# chariot_comms_a2.net
KiCad netlist of a schematic drawn in EAGLE
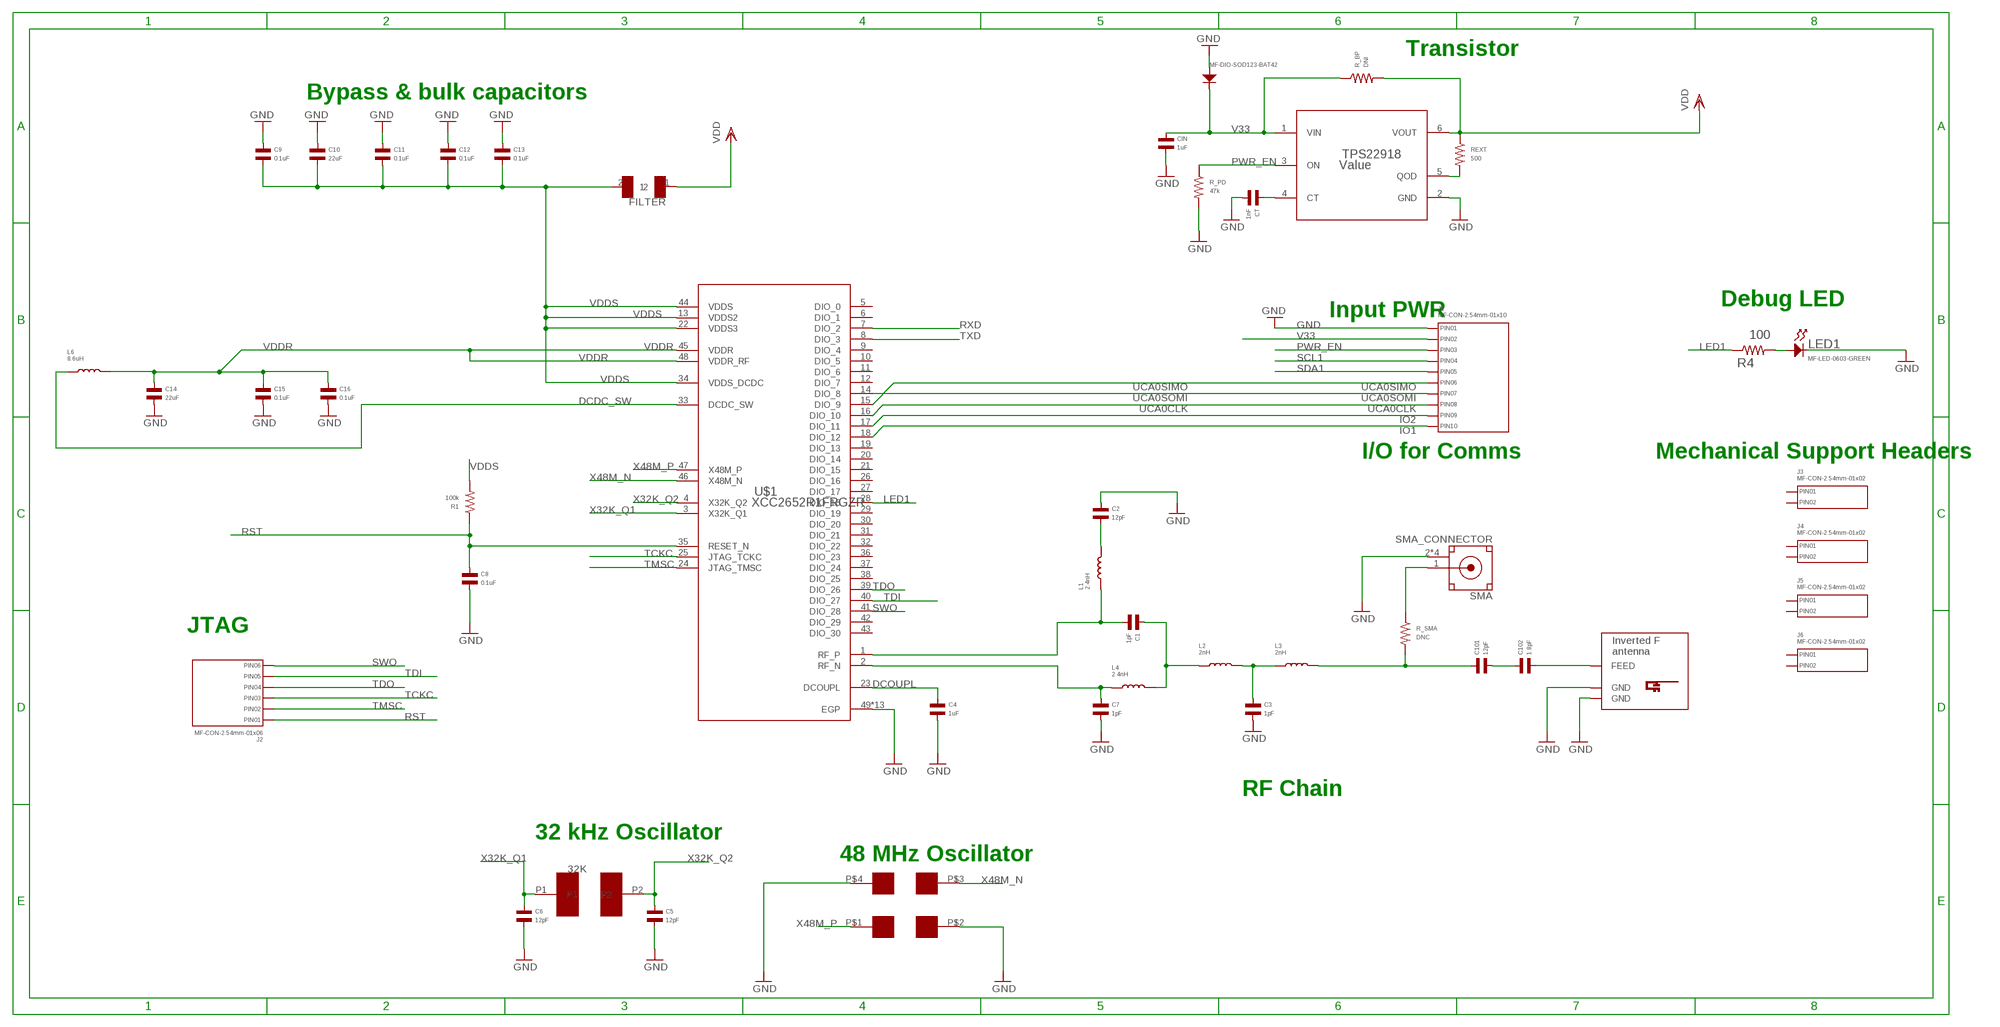
[diagram p0: schematic, sheet 1]

(export (version "E")
  (design (tool "Eeschema 10.0.6"))
  (components
    (comp (ref "32K")
      (value "FC-135")
      (footprint "eagle-import:FC-135")
      (libsource (lib "eagle-import") (part "FC-135"))
    )
    (comp (ref "48M")
      (value "NX2016SA-48M-EXS00A-CS05517")
      (footprint "eagle-import:NX2016SA-48M-EXS00A-CS05517")
      (libsource (lib "eagle-import") (part "NX2016SA-48M-EXS00A-CS05517"))
    )
    (comp (ref "C1")
      (value "1pF")
      (footprint "eagle-import:C0603")
      (libsource (lib "eagle-import") (part "CAPACITOR_NP_0603"))
    )
    (comp (ref "C2")
      (value "12pF")
      (footprint "eagle-import:C0603")
      (libsource (lib "eagle-import") (part "CAPACITOR_NP_0603"))
    )
    (comp (ref "C3")
      (value "1pF")
      (footprint "eagle-import:C0603")
      (libsource (lib "eagle-import") (part "CAPACITOR_NP_0603"))
    )
    (comp (ref "C4")
      (value "1uF")
      (footprint "eagle-import:C0603")
      (libsource (lib "eagle-import") (part "CAPACITOR_NP_0603"))
    )
    (comp (ref "C5")
      (value "12pF")
      (footprint "eagle-import:C0603")
      (libsource (lib "eagle-import") (part "CAPACITOR_NP_0603"))
    )
    (comp (ref "C6")
      (value "12pF")
      (footprint "eagle-import:C0603")
      (libsource (lib "eagle-import") (part "CAPACITOR_NP_0603"))
    )
    (comp (ref "C7")
      (value "1pF")
      (footprint "eagle-import:C0603")
      (libsource (lib "eagle-import") (part "CAPACITOR_NP_0603"))
    )
    (comp (ref "C8")
      (value "0.1uF")
      (footprint "eagle-import:C0603")
      (libsource (lib "eagle-import") (part "CAPACITOR_NP_0603"))
    )
    (comp (ref "C9")
      (value "0.1uF")
      (footprint "eagle-import:C0603")
      (libsource (lib "eagle-import") (part "CAPACITOR_NP_0603"))
    )
    (comp (ref "C10")
      (value "22uF")
      (footprint "eagle-import:C0603")
      (libsource (lib "eagle-import") (part "CAPACITOR_NP_0603"))
    )
    (comp (ref "C11")
      (value "0.1uF")
      (footprint "eagle-import:C0603")
      (libsource (lib "eagle-import") (part "CAPACITOR_NP_0603"))
    )
    (comp (ref "C12")
      (value "0.1uF")
      (footprint "eagle-import:C0603")
      (libsource (lib "eagle-import") (part "CAPACITOR_NP_0603"))
    )
    (comp (ref "C13")
      (value "0.1uF")
      (footprint "eagle-import:C0603")
      (libsource (lib "eagle-import") (part "CAPACITOR_NP_0603"))
    )
    (comp (ref "C14")
      (value "22uF")
      (footprint "eagle-import:C0603")
      (libsource (lib "eagle-import") (part "CAPACITOR_NP_0603"))
    )
    (comp (ref "C15")
      (value "0.1uF")
      (footprint "eagle-import:C0603")
      (libsource (lib "eagle-import") (part "CAPACITOR_NP_0603"))
    )
    (comp (ref "C16")
      (value "0.1uF")
      (footprint "eagle-import:C0603")
      (libsource (lib "eagle-import") (part "CAPACITOR_NP_0603"))
    )
    (comp (ref "C101")
      (value "12pF")
      (footprint "eagle-import:C0603")
      (libsource (lib "eagle-import") (part "CAPACITOR_NP_0603"))
    )
    (comp (ref "C102")
      (value "1.8pF")
      (footprint "eagle-import:C0603")
      (libsource (lib "eagle-import") (part "CAPACITOR_NP_0603"))
    )
    (comp (ref "CIN")
      (value "1uF")
      (footprint "eagle-import:C0603")
      (libsource (lib "eagle-import") (part "CAPACITOR_NP_0603"))
    )
    (comp (ref "CT")
      (value "1nF")
      (footprint "eagle-import:C0603")
      (libsource (lib "eagle-import") (part "CAPACITOR_NP_0603"))
    )
    (comp (ref "D1")
      (value "MF-DIO-SOD123-BAT42")
      (footprint "eagle-import:SOD-123")
      (fields (field (name "HOUSEPART") "YES"))
      (libsource (lib "eagle-import") (part "DIODES_SOD-123_BAT42"))
    )
    (comp (ref "FILTER")
      (value "BLM18")
      (footprint "eagle-import:BLM18")
      (libsource (lib "eagle-import") (part "BLM18"))
    )
    (comp (ref "J1")
      (value "MF-CON-2.54mm-01x10")
      (footprint "eagle-import:PTH_2.54MM_01X10")
      (fields (field (name "HOUSEPART") "YES"))
      (libsource (lib "eagle-import") (part "CON_01X10_PTH_2.54MM"))
    )
    (comp (ref "J2")
      (value "MF-CON-2.54mm-01x06")
      (footprint "eagle-import:PTH_2.54MM_01X06")
      (fields (field (name "HOUSEPART") "YES"))
      (libsource (lib "eagle-import") (part "CON_01X06_PTH_2.54MM"))
    )
    (comp (ref "J3")
      (value "MF-CON-2.54mm-01x02")
      (footprint "eagle-import:PTH_2.54MM_01X02")
      (fields (field (name "HOUSEPART") "YES"))
      (libsource (lib "eagle-import") (part "CON_01X02_PTH_2.54MM"))
    )
    (comp (ref "J4")
      (value "MF-CON-2.54mm-01x02")
      (footprint "eagle-import:PTH_2.54MM_01X02")
      (fields (field (name "HOUSEPART") "YES"))
      (libsource (lib "eagle-import") (part "CON_01X02_PTH_2.54MM"))
    )
    (comp (ref "J5")
      (value "MF-CON-2.54mm-01x02")
      (footprint "eagle-import:PTH_2.54MM_01X02")
      (fields (field (name "HOUSEPART") "YES"))
      (libsource (lib "eagle-import") (part "CON_01X02_PTH_2.54MM"))
    )
    (comp (ref "J6")
      (value "MF-CON-2.54mm-01x02")
      (footprint "eagle-import:PTH_2.54MM_01X02")
      (fields (field (name "HOUSEPART") "YES"))
      (libsource (lib "eagle-import") (part "CON_01X02_PTH_2.54MM"))
    )
    (comp (ref "L1")
      (value "2.4nH")
      (footprint "eagle-import:L0603")
      (libsource (lib "eagle-import") (part "INDUCTOR_0603"))
    )
    (comp (ref "L2")
      (value "2nH")
      (footprint "eagle-import:L0603")
      (libsource (lib "eagle-import") (part "INDUCTOR_0603"))
    )
    (comp (ref "L3")
      (value "2nH")
      (footprint "eagle-import:L0603")
      (libsource (lib "eagle-import") (part "INDUCTOR_0603"))
    )
    (comp (ref "L4")
      (value "2.4nH")
      (footprint "eagle-import:L0603")
      (libsource (lib "eagle-import") (part "INDUCTOR_0603"))
    )
    (comp (ref "L6")
      (value "8.6uH")
      (footprint "eagle-import:L0603")
      (libsource (lib "eagle-import") (part "INDUCTOR_0603"))
    )
    (comp (ref "LED1")
      (value "MF-LED-0603-GREEN")
      (footprint "eagle-import:LED0603")
      (fields (field (name "HOUSEPART") "YES"))
      (libsource (lib "eagle-import") (part "LED_SINGLE-0603-GREEN"))
    )
    (comp (ref "R1")
      (value "100k")
      (footprint "eagle-import:R0603")
      (libsource (lib "eagle-import") (part "RESISTOR_0603"))
    )
    (comp (ref "R4")
      (value "100")
      (footprint "eagle-import:R0603")
      (libsource (lib "eagle-import") (part "RESISTOR_0603"))
    )
    (comp (ref "REXT")
      (value "500")
      (footprint "eagle-import:R0603")
      (libsource (lib "eagle-import") (part "RESISTOR_0603"))
    )
    (comp (ref "R_BP")
      (value "DNI")
      (footprint "eagle-import:R0603")
      (libsource (lib "eagle-import") (part "RESISTOR_0603"))
    )
    (comp (ref "R_PD")
      (value "47k")
      (footprint "eagle-import:R0603")
      (libsource (lib "eagle-import") (part "RESISTOR_0603"))
    )
    (comp (ref "R_SMA")
      (value "DNC")
      (footprint "eagle-import:R0603")
      (libsource (lib "eagle-import") (part "RESISTOR_0603"))
    )
    (comp (ref "SMA")
      (value "SMA_CONNECTOR")
      (footprint "eagle-import:LPRS_SMA_CONNECTOR")
      (fields (field (name "MF") "LPRS") (field (name "MP") "SMA CONNECTOR"))
      (libsource (lib "eagle-import") (part "SMA_CONNECTOR"))
    )
    (comp (ref "TPS22918")
      (value "Value")
      (footprint "eagle-import:DBV0006A_N")
      (fields (field (name "MANUFACTURER") "Texas Instruments") (field (name "PARTNUMBER") "TPS22918TDBVRQ1"))
      (libsource (lib "eagle-import") (part "TPS22918TDBVRQ1"))
    )
    (comp (ref "U$1")
      (value "XCC2652R1FRGZR")
      (footprint "eagle-import:RGZ0048A")
      (libsource (lib "eagle-import") (part "XCC2652R1FRGZR"))
    )
    (comp (ref "U$2")
      (value "INVERTED_F_ANTENNA+5")
      (footprint "eagle-import:DN007+5")
      (libsource (lib "eagle-import") (part "INVERTED_F_ANTENNA+5"))
    )
  )
  (nets
    (net (code "1") (name "/DCDC_SW") (class "Default")
      (node (ref "L6") (pin "P$1") (pinfunction "P$1_P$1") (pintype "passive"))
      (node (ref "U$1") (pin "33") (pinfunction "DCDC_SW_33") (pintype "power_in"))
    )
    (net (code "2") (name "/DCOUPL") (class "Default")
      (node (ref "C4") (pin "P$1") (pinfunction "P$1_P$1") (pintype "passive"))
      (node (ref "U$1") (pin "23") (pinfunction "DCOUPL_23") (pintype "power_in"))
    )
    (net (code "3") (name "/IO1") (class "Default")
      (node (ref "J1") (pin "P$10") (pinfunction "PIN10_P$10") (pintype "bidirectional"))
      (node (ref "U$1") (pin "18") (pinfunction "DIO_12_18") (pintype "bidirectional"))
    )
    (net (code "4") (name "/IO2") (class "Default")
      (node (ref "J1") (pin "P$9") (pinfunction "PIN9_P$9") (pintype "bidirectional"))
      (node (ref "U$1") (pin "17") (pinfunction "DIO_11_17") (pintype "bidirectional"))
    )
    (net (code "5") (name "/LED1") (class "Default")
      (node (ref "R4") (pin "P$1") (pinfunction "P$1_P$1") (pintype "passive"))
      (node (ref "U$1") (pin "28") (pinfunction "DIO_18_28") (pintype "bidirectional"))
    )
    (net (code "6") (name "/PWR_EN") (class "Default")
      (node (ref "J1") (pin "P$3") (pinfunction "PIN3_P$3") (pintype "bidirectional"))
      (node (ref "R_PD") (pin "P$1") (pinfunction "P$1_P$1") (pintype "passive"))
      (node (ref "TPS22918") (pin "3") (pinfunction "ON_3") (pintype "input"))
    )
    (net (code "7") (name "/RST") (class "Default")
      (node (ref "C8") (pin "P$1") (pinfunction "P$1_P$1") (pintype "passive"))
      (node (ref "J2") (pin "P$1") (pinfunction "PIN1_P$1") (pintype "bidirectional"))
      (node (ref "R1") (pin "P$1") (pinfunction "P$1_P$1") (pintype "passive"))
      (node (ref "U$1") (pin "35") (pinfunction "RESET_N_35") (pintype "input"))
    )
    (net (code "8") (name "/RXD") (class "Default")
      (node (ref "U$1") (pin "7") (pinfunction "DIO_2_7") (pintype "bidirectional"))
    )
    (net (code "9") (name "/SCL1") (class "Default")
      (node (ref "J1") (pin "P$4") (pinfunction "PIN4_P$4") (pintype "bidirectional"))
    )
    (net (code "10") (name "/SDA1") (class "Default")
      (node (ref "J1") (pin "P$5") (pinfunction "PIN5_P$5") (pintype "bidirectional"))
    )
    (net (code "11") (name "/SWO") (class "Default")
      (node (ref "J2") (pin "P$6") (pinfunction "PIN6_P$6") (pintype "bidirectional"))
      (node (ref "U$1") (pin "41") (pinfunction "DIO_28_41") (pintype "bidirectional"))
    )
    (net (code "12") (name "/TCKC") (class "Default")
      (node (ref "J2") (pin "P$3") (pinfunction "PIN3_P$3") (pintype "bidirectional"))
      (node (ref "U$1") (pin "25") (pinfunction "JTAG_TCKC_25") (pintype "bidirectional"))
    )
    (net (code "13") (name "/TDI") (class "Default")
      (node (ref "J2") (pin "P$5") (pinfunction "PIN5_P$5") (pintype "bidirectional"))
      (node (ref "U$1") (pin "40") (pinfunction "DIO_27_40") (pintype "bidirectional"))
    )
    (net (code "14") (name "/TDO") (class "Default")
      (node (ref "J2") (pin "P$4") (pinfunction "PIN4_P$4") (pintype "bidirectional"))
      (node (ref "U$1") (pin "39") (pinfunction "DIO_26_39") (pintype "bidirectional"))
    )
    (net (code "15") (name "/TMSC") (class "Default")
      (node (ref "J2") (pin "P$2") (pinfunction "PIN2_P$2") (pintype "bidirectional"))
      (node (ref "U$1") (pin "24") (pinfunction "JTAG_TMSC_24") (pintype "bidirectional"))
    )
    (net (code "16") (name "/TXD") (class "Default")
      (node (ref "U$1") (pin "8") (pinfunction "DIO_3_8") (pintype "bidirectional"))
    )
    (net (code "17") (name "/UCA0CLK") (class "Default")
      (node (ref "J1") (pin "P$8") (pinfunction "PIN8_P$8") (pintype "bidirectional"))
      (node (ref "U$1") (pin "16") (pinfunction "DIO_10_16") (pintype "bidirectional"))
    )
    (net (code "18") (name "/UCA0SIMO") (class "Default")
      (node (ref "J1") (pin "P$6") (pinfunction "PIN6_P$6") (pintype "bidirectional"))
      (node (ref "U$1") (pin "15") (pinfunction "DIO_9_15") (pintype "bidirectional"))
    )
    (net (code "19") (name "/UCA0SOMI") (class "Default")
      (node (ref "J1") (pin "P$7") (pinfunction "PIN7_P$7") (pintype "bidirectional"))
      (node (ref "U$1") (pin "14") (pinfunction "DIO_8_14") (pintype "bidirectional"))
    )
    (net (code "20") (name "/V33") (class "Default")
      (node (ref "CIN") (pin "P$1") (pinfunction "P$1_P$1") (pintype "passive"))
      (node (ref "D1") (pin "CATHODE") (pinfunction "CATHODE_CATHODE") (pintype "bidirectional"))
      (node (ref "J1") (pin "P$2") (pinfunction "PIN2_P$2") (pintype "bidirectional"))
      (node (ref "R_BP") (pin "P$1") (pinfunction "P$1_P$1") (pintype "passive"))
      (node (ref "TPS22918") (pin "1") (pinfunction "VIN_1") (pintype "power_in"))
    )
    (net (code "21") (name "/VDDR") (class "Default")
      (node (ref "C14") (pin "P$1") (pinfunction "P$1_P$1") (pintype "passive"))
      (node (ref "C15") (pin "P$1") (pinfunction "P$1_P$1") (pintype "passive"))
      (node (ref "C16") (pin "P$1") (pinfunction "P$1_P$1") (pintype "passive"))
      (node (ref "L6") (pin "P$2") (pinfunction "P$2_P$2") (pintype "passive"))
      (node (ref "U$1") (pin "45") (pinfunction "VDDR_45") (pintype "power_in"))
      (node (ref "U$1") (pin "48") (pinfunction "VDDR_RF_48") (pintype "power_in"))
    )
    (net (code "22") (name "/VDDS") (class "Default")
      (node (ref "C10") (pin "P$2") (pinfunction "P$2_P$2") (pintype "passive"))
      (node (ref "C11") (pin "P$2") (pinfunction "P$2_P$2") (pintype "passive"))
      (node (ref "C12") (pin "P$2") (pinfunction "P$2_P$2") (pintype "passive"))
      (node (ref "C13") (pin "P$2") (pinfunction "P$2_P$2") (pintype "passive"))
      (node (ref "C9") (pin "P$2") (pinfunction "P$2_P$2") (pintype "passive"))
      (node (ref "FILTER") (pin "2") (pinfunction "2_2") (pintype "bidirectional"))
      (node (ref "R1") (pin "P$2") (pinfunction "P$2_P$2") (pintype "passive"))
      (node (ref "U$1") (pin "13") (pinfunction "VDDS2_13") (pintype "power_in"))
      (node (ref "U$1") (pin "22") (pinfunction "VDDS3_22") (pintype "power_in"))
      (node (ref "U$1") (pin "34") (pinfunction "VDDS_DCDC_34") (pintype "power_in"))
      (node (ref "U$1") (pin "44") (pinfunction "VDDS_44") (pintype "power_in"))
    )
    (net (code "23") (name "/X32K_Q1") (class "Default")
      (node (ref "32K") (pin "P1") (pinfunction "P1_P1") (pintype "bidirectional"))
      (node (ref "C6") (pin "P$1") (pinfunction "P$1_P$1") (pintype "passive"))
      (node (ref "U$1") (pin "3") (pinfunction "X32K_Q1_3") (pintype "bidirectional"))
    )
    (net (code "24") (name "/X32K_Q2") (class "Default")
      (node (ref "32K") (pin "P2") (pinfunction "P2_P2") (pintype "bidirectional"))
      (node (ref "C5") (pin "P$1") (pinfunction "P$1_P$1") (pintype "passive"))
      (node (ref "U$1") (pin "4") (pinfunction "X32K_Q2_4") (pintype "bidirectional"))
    )
    (net (code "25") (name "/X48M_N") (class "Default")
      (node (ref "48M") (pin "P$3") (pinfunction "P$3_P$3") (pintype "bidirectional"))
      (node (ref "U$1") (pin "46") (pinfunction "X48M_N_46") (pintype "bidirectional"))
    )
    (net (code "26") (name "/X48M_P") (class "Default")
      (node (ref "48M") (pin "P$1") (pinfunction "P$1_P$1") (pintype "bidirectional"))
      (node (ref "U$1") (pin "47") (pinfunction "X48M_P_47") (pintype "bidirectional"))
    )
    (net (code "27") (name "GND") (class "Default")
      (node (ref "48M") (pin "P$2") (pinfunction "P$2_P$2") (pintype "bidirectional"))
      (node (ref "48M") (pin "P$4") (pinfunction "P$4_P$4") (pintype "bidirectional"))
      (node (ref "C10") (pin "P$1") (pinfunction "P$1_P$1") (pintype "passive"))
      (node (ref "C11") (pin "P$1") (pinfunction "P$1_P$1") (pintype "passive"))
      (node (ref "C12") (pin "P$1") (pinfunction "P$1_P$1") (pintype "passive"))
      (node (ref "C13") (pin "P$1") (pinfunction "P$1_P$1") (pintype "passive"))
      (node (ref "C14") (pin "P$2") (pinfunction "P$2_P$2") (pintype "passive"))
      (node (ref "C15") (pin "P$2") (pinfunction "P$2_P$2") (pintype "passive"))
      (node (ref "C16") (pin "P$2") (pinfunction "P$2_P$2") (pintype "passive"))
      (node (ref "C2") (pin "P$1") (pinfunction "P$1_P$1") (pintype "passive"))
      (node (ref "C3") (pin "P$2") (pinfunction "P$2_P$2") (pintype "passive"))
      (node (ref "C4") (pin "P$2") (pinfunction "P$2_P$2") (pintype "passive"))
      (node (ref "C5") (pin "P$2") (pinfunction "P$2_P$2") (pintype "passive"))
      (node (ref "C6") (pin "P$2") (pinfunction "P$2_P$2") (pintype "passive"))
      (node (ref "C7") (pin "P$2") (pinfunction "P$2_P$2") (pintype "passive"))
      (node (ref "C8") (pin "P$2") (pinfunction "P$2_P$2") (pintype "passive"))
      (node (ref "C9") (pin "P$1") (pinfunction "P$1_P$1") (pintype "passive"))
      (node (ref "CIN") (pin "P$2") (pinfunction "P$2_P$2") (pintype "passive"))
      (node (ref "CT") (pin "P$2") (pinfunction "P$2_P$2") (pintype "passive"))
      (node (ref "D1") (pin "ANODE") (pinfunction "ANODE_ANODE") (pintype "bidirectional"))
      (node (ref "J1") (pin "P$1") (pinfunction "PIN1_P$1") (pintype "bidirectional"))
      (node (ref "LED1") (pin "CATHODE") (pinfunction "CATHODE_CATHODE") (pintype "power_in"))
      (node (ref "R_PD") (pin "P$2") (pinfunction "P$2_P$2") (pintype "passive"))
      (node (ref "SMA") (pin "2") (pinfunction "GND_2") (pintype "passive"))
      (node (ref "SMA") (pin "3") (pinfunction "GND_3") (pintype "passive"))
      (node (ref "SMA") (pin "4") (pinfunction "GND_4") (pintype "passive"))
      (node (ref "SMA") (pin "5") (pinfunction "GND_5") (pintype "passive"))
      (node (ref "TPS22918") (pin "2") (pinfunction "GND_2") (pintype "power_in"))
      (node (ref "U$1") (pin "49") (pinfunction "EGP_49") (pintype "power_in"))
      (node (ref "U$1") (pin "V1") (pinfunction "EGP_V1") (pintype "power_in"))
      (node (ref "U$1") (pin "V10") (pinfunction "EGP_V10") (pintype "power_in"))
      (node (ref "U$1") (pin "V11") (pinfunction "EGP_V11") (pintype "power_in"))
      (node (ref "U$1") (pin "V12") (pinfunction "EGP_V12") (pintype "power_in"))
      (node (ref "U$1") (pin "V2") (pinfunction "EGP_V2") (pintype "power_in"))
      (node (ref "U$1") (pin "V3") (pinfunction "EGP_V3") (pintype "power_in"))
      (node (ref "U$1") (pin "V4") (pinfunction "EGP_V4") (pintype "power_in"))
      (node (ref "U$1") (pin "V5") (pinfunction "EGP_V5") (pintype "power_in"))
      (node (ref "U$1") (pin "V6") (pinfunction "EGP_V6") (pintype "power_in"))
      (node (ref "U$1") (pin "V7") (pinfunction "EGP_V7") (pintype "power_in"))
      (node (ref "U$1") (pin "V8") (pinfunction "EGP_V8") (pintype "power_in"))
      (node (ref "U$1") (pin "V9") (pinfunction "EGP_V9") (pintype "power_in"))
      (node (ref "U$2") (pin "GND") (pinfunction "GND_GND") (pintype "bidirectional"))
      (node (ref "U$2") (pin "GND@1") (pinfunction "GND_GND@1") (pintype "bidirectional"))
    )
    (net (code "28") (name "Net-(C1-PadP$1)") (class "Default")
      (node (ref "C1") (pin "P$1") (pinfunction "P$1_P$1") (pintype "passive"))
      (node (ref "L2") (pin "P$1") (pinfunction "P$1_P$1") (pintype "passive"))
      (node (ref "L4") (pin "P$2") (pinfunction "P$2_P$2") (pintype "passive"))
    )
    (net (code "29") (name "Net-(C2-PadP$2)") (class "Default")
      (node (ref "C2") (pin "P$2") (pinfunction "P$2_P$2") (pintype "passive"))
      (node (ref "L1") (pin "P$2") (pinfunction "P$2_P$2") (pintype "passive"))
    )
    (net (code "30") (name "Net-(C3-PadP$1)") (class "Default")
      (node (ref "C3") (pin "P$1") (pinfunction "P$1_P$1") (pintype "passive"))
      (node (ref "L2") (pin "P$2") (pinfunction "P$2_P$2") (pintype "passive"))
      (node (ref "L3") (pin "P$1") (pinfunction "P$1_P$1") (pintype "passive"))
    )
    (net (code "31") (name "Net-(C101-PadP$1)") (class "Default")
      (node (ref "C101") (pin "P$1") (pinfunction "P$1_P$1") (pintype "passive"))
      (node (ref "L3") (pin "P$2") (pinfunction "P$2_P$2") (pintype "passive"))
      (node (ref "R_SMA") (pin "P$2") (pinfunction "P$2_P$2") (pintype "passive"))
    )
    (net (code "32") (name "Net-(C101-PadP$2)") (class "Default")
      (node (ref "C101") (pin "P$2") (pinfunction "P$2_P$2") (pintype "passive"))
      (node (ref "C102") (pin "P$1") (pinfunction "P$1_P$1") (pintype "passive"))
    )
    (net (code "33") (name "Net-(C102-PadP$2)") (class "Default")
      (node (ref "C102") (pin "P$2") (pinfunction "P$2_P$2") (pintype "passive"))
      (node (ref "U$2") (pin "FEED") (pinfunction "FEED_FEED") (pintype "bidirectional"))
    )
    (net (code "34") (name "Net-(LED1-PadANODE)") (class "Default")
      (node (ref "LED1") (pin "ANODE") (pinfunction "ANODE_ANODE") (pintype "power_in"))
      (node (ref "R4") (pin "P$2") (pinfunction "P$2_P$2") (pintype "passive"))
    )
    (net (code "35") (name "Net-(SMA-SIG)") (class "Default")
      (node (ref "R_SMA") (pin "P$1") (pinfunction "P$1_P$1") (pintype "passive"))
      (node (ref "SMA") (pin "1") (pinfunction "SIG_1") (pintype "passive"))
    )
    (net (code "36") (name "Net-(TPS22918-CT)") (class "Default")
      (node (ref "CT") (pin "P$1") (pinfunction "P$1_P$1") (pintype "passive"))
      (node (ref "TPS22918") (pin "4") (pinfunction "CT_4") (pintype "output"))
    )
    (net (code "37") (name "Net-(TPS22918-QOD)") (class "Default")
      (node (ref "REXT") (pin "P$2") (pinfunction "P$2_P$2") (pintype "passive"))
      (node (ref "TPS22918") (pin "5") (pinfunction "QOD_5") (pintype "input"))
    )
    (net (code "38") (name "Net-(U$1-RF_N)") (class "Default")
      (node (ref "C7") (pin "P$1") (pinfunction "P$1_P$1") (pintype "passive"))
      (node (ref "L4") (pin "P$1") (pinfunction "P$1_P$1") (pintype "passive"))
      (node (ref "U$1") (pin "2") (pinfunction "RF_N_2") (pintype "bidirectional"))
    )
    (net (code "39") (name "Net-(U$1-RF_P)") (class "Default")
      (node (ref "C1") (pin "P$2") (pinfunction "P$2_P$2") (pintype "passive"))
      (node (ref "L1") (pin "P$1") (pinfunction "P$1_P$1") (pintype "passive"))
      (node (ref "U$1") (pin "1") (pinfunction "RF_P_1") (pintype "bidirectional"))
    )
    (net (code "40") (name "VDD") (class "Default")
      (node (ref "FILTER") (pin "1") (pinfunction "1_1") (pintype "bidirectional"))
      (node (ref "REXT") (pin "P$1") (pinfunction "P$1_P$1") (pintype "passive"))
      (node (ref "R_BP") (pin "P$2") (pinfunction "P$2_P$2") (pintype "passive"))
      (node (ref "TPS22918") (pin "6") (pinfunction "VOUT_6") (pintype "power_in"))
    )
    (net (code "41") (name "unconnected-(J3-PIN1-PadP$1)") (class "Default")
      (node (ref "J3") (pin "P$1") (pinfunction "PIN1_P$1") (pintype "bidirectional"))
    )
    (net (code "42") (name "unconnected-(J3-PIN2-PadP$2)") (class "Default")
      (node (ref "J3") (pin "P$2") (pinfunction "PIN2_P$2") (pintype "bidirectional"))
    )
    (net (code "43") (name "unconnected-(J4-PIN1-PadP$1)") (class "Default")
      (node (ref "J4") (pin "P$1") (pinfunction "PIN1_P$1") (pintype "bidirectional"))
    )
    (net (code "44") (name "unconnected-(J4-PIN2-PadP$2)") (class "Default")
      (node (ref "J4") (pin "P$2") (pinfunction "PIN2_P$2") (pintype "bidirectional"))
    )
    (net (code "45") (name "unconnected-(J5-PIN1-PadP$1)") (class "Default")
      (node (ref "J5") (pin "P$1") (pinfunction "PIN1_P$1") (pintype "bidirectional"))
    )
    (net (code "46") (name "unconnected-(J5-PIN2-PadP$2)") (class "Default")
      (node (ref "J5") (pin "P$2") (pinfunction "PIN2_P$2") (pintype "bidirectional"))
    )
    (net (code "47") (name "unconnected-(J6-PIN1-PadP$1)") (class "Default")
      (node (ref "J6") (pin "P$1") (pinfunction "PIN1_P$1") (pintype "bidirectional"))
    )
    (net (code "48") (name "unconnected-(J6-PIN2-PadP$2)") (class "Default")
      (node (ref "J6") (pin "P$2") (pinfunction "PIN2_P$2") (pintype "bidirectional"))
    )
    (net (code "49") (name "unconnected-(U$1-DIO_0-Pad5)") (class "Default")
      (node (ref "U$1") (pin "5") (pinfunction "DIO_0_5") (pintype "bidirectional"))
    )
    (net (code "50") (name "unconnected-(U$1-DIO_1-Pad6)") (class "Default")
      (node (ref "U$1") (pin "6") (pinfunction "DIO_1_6") (pintype "bidirectional"))
    )
    (net (code "51") (name "unconnected-(U$1-DIO_4-Pad9)") (class "Default")
      (node (ref "U$1") (pin "9") (pinfunction "DIO_4_9") (pintype "bidirectional"))
    )
    (net (code "52") (name "unconnected-(U$1-DIO_5-Pad10)") (class "Default")
      (node (ref "U$1") (pin "10") (pinfunction "DIO_5_10") (pintype "bidirectional"))
    )
    (net (code "53") (name "unconnected-(U$1-DIO_6-Pad11)") (class "Default")
      (node (ref "U$1") (pin "11") (pinfunction "DIO_6_11") (pintype "bidirectional"))
    )
    (net (code "54") (name "unconnected-(U$1-DIO_7-Pad12)") (class "Default")
      (node (ref "U$1") (pin "12") (pinfunction "DIO_7_12") (pintype "bidirectional"))
    )
    (net (code "55") (name "unconnected-(U$1-DIO_13-Pad19)") (class "Default")
      (node (ref "U$1") (pin "19") (pinfunction "DIO_13_19") (pintype "bidirectional"))
    )
    (net (code "56") (name "unconnected-(U$1-DIO_14-Pad20)") (class "Default")
      (node (ref "U$1") (pin "20") (pinfunction "DIO_14_20") (pintype "bidirectional"))
    )
    (net (code "57") (name "unconnected-(U$1-DIO_15-Pad21)") (class "Default")
      (node (ref "U$1") (pin "21") (pinfunction "DIO_15_21") (pintype "bidirectional"))
    )
    (net (code "58") (name "unconnected-(U$1-DIO_16-Pad26)") (class "Default")
      (node (ref "U$1") (pin "26") (pinfunction "DIO_16_26") (pintype "bidirectional"))
    )
    (net (code "59") (name "unconnected-(U$1-DIO_17-Pad27)") (class "Default")
      (node (ref "U$1") (pin "27") (pinfunction "DIO_17_27") (pintype "bidirectional"))
    )
    (net (code "60") (name "unconnected-(U$1-DIO_19-Pad29)") (class "Default")
      (node (ref "U$1") (pin "29") (pinfunction "DIO_19_29") (pintype "bidirectional"))
    )
    (net (code "61") (name "unconnected-(U$1-DIO_20-Pad30)") (class "Default")
      (node (ref "U$1") (pin "30") (pinfunction "DIO_20_30") (pintype "bidirectional"))
    )
    (net (code "62") (name "unconnected-(U$1-DIO_21-Pad31)") (class "Default")
      (node (ref "U$1") (pin "31") (pinfunction "DIO_21_31") (pintype "bidirectional"))
    )
    (net (code "63") (name "unconnected-(U$1-DIO_22-Pad32)") (class "Default")
      (node (ref "U$1") (pin "32") (pinfunction "DIO_22_32") (pintype "bidirectional"))
    )
    (net (code "64") (name "unconnected-(U$1-DIO_23-Pad36)") (class "Default")
      (node (ref "U$1") (pin "36") (pinfunction "DIO_23_36") (pintype "bidirectional"))
    )
    (net (code "65") (name "unconnected-(U$1-DIO_24-Pad37)") (class "Default")
      (node (ref "U$1") (pin "37") (pinfunction "DIO_24_37") (pintype "bidirectional"))
    )
    (net (code "66") (name "unconnected-(U$1-DIO_25-Pad38)") (class "Default")
      (node (ref "U$1") (pin "38") (pinfunction "DIO_25_38") (pintype "bidirectional"))
    )
    (net (code "67") (name "unconnected-(U$1-DIO_29-Pad42)") (class "Default")
      (node (ref "U$1") (pin "42") (pinfunction "DIO_29_42") (pintype "bidirectional"))
    )
    (net (code "68") (name "unconnected-(U$1-DIO_30-Pad43)") (class "Default")
      (node (ref "U$1") (pin "43") (pinfunction "DIO_30_43") (pintype "bidirectional"))
    )
  )
)
